# SMT_SW_PTS_820_Button.net
KiCad netlist of a schematic drawn in Altium Designer
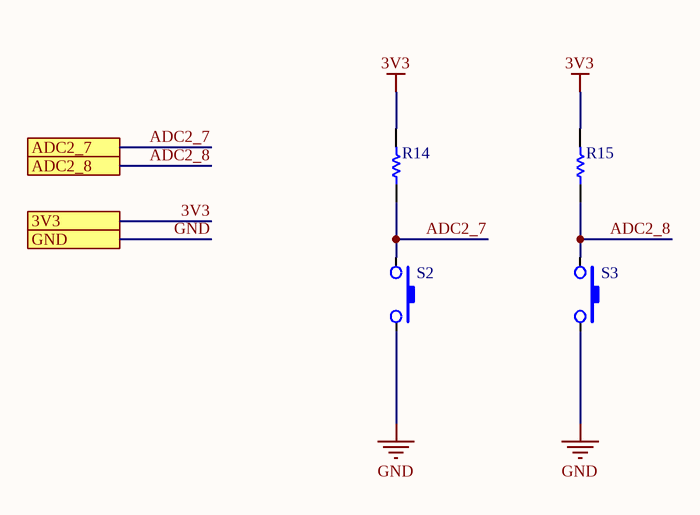
[diagram p0: SMT_SW_PTS_820_Button.SchDoc]

(export (version "E")
  (design (tool "Eeschema 10.0.6"))
  (components
    (comp (ref "R14")
      (value "RK73B2ATTD103J")
      (footprint "RESC2013X60X30NL20T20")
      (fields (field (name "MANUFACTURER") "KOA Speer"))
      (libsource (lib "Altium Content Vault") (part "RES"))
    )
    (comp (ref "R15")
      (value "RK73B2ATTD103J")
      (footprint "RESC2013X60X30NL20T20")
      (fields (field (name "MANUFACTURER") "KOA Speer"))
      (libsource (lib "Altium Content Vault") (part "RES"))
    )
    (comp (ref "S2")
      (value "PTS820J25MSMTRLFS")
      (footprint "SMT_SW_PTS_820")
      (description "Tactile Switch SPST-NO Top Actuated Surface Moun")
      (libsource (lib "LIB_FIT") (part "PTS820J25MSMTRLFS"))
    )
    (comp (ref "S3")
      (value "PTS820J25MSMTRLFS")
      (footprint "SMT_SW_PTS_820")
      (description "Tactile Switch SPST-NO Top Actuated Surface Moun")
      (libsource (lib "LIB_FIT") (part "PTS820J25MSMTRLFS"))
    )
  )
  (nets
    (net (code "1") (name "/ADC2_7") (class "Default")
      (node (ref "R14") (pin "1") (pinfunction "1_1") (pintype "passive"))
      (node (ref "S2") (pin "1") (pinfunction "1_1") (pintype "passive"))
    )
    (net (code "2") (name "/ADC2_8") (class "Default")
      (node (ref "R15") (pin "1") (pinfunction "1_1") (pintype "passive"))
      (node (ref "S3") (pin "1") (pinfunction "1_1") (pintype "passive"))
    )
    (net (code "3") (name "3V3") (class "Default")
      (node (ref "R14") (pin "2") (pinfunction "2_2") (pintype "passive"))
      (node (ref "R15") (pin "2") (pinfunction "2_2") (pintype "passive"))
    )
    (net (code "4") (name "GND") (class "Default")
      (node (ref "S2") (pin "2") (pinfunction "2_2") (pintype "passive"))
      (node (ref "S3") (pin "2") (pinfunction "2_2") (pintype "passive"))
    )
  )
)
